# source_eagle.net
KiCad netlist of a schematic drawn in EAGLE
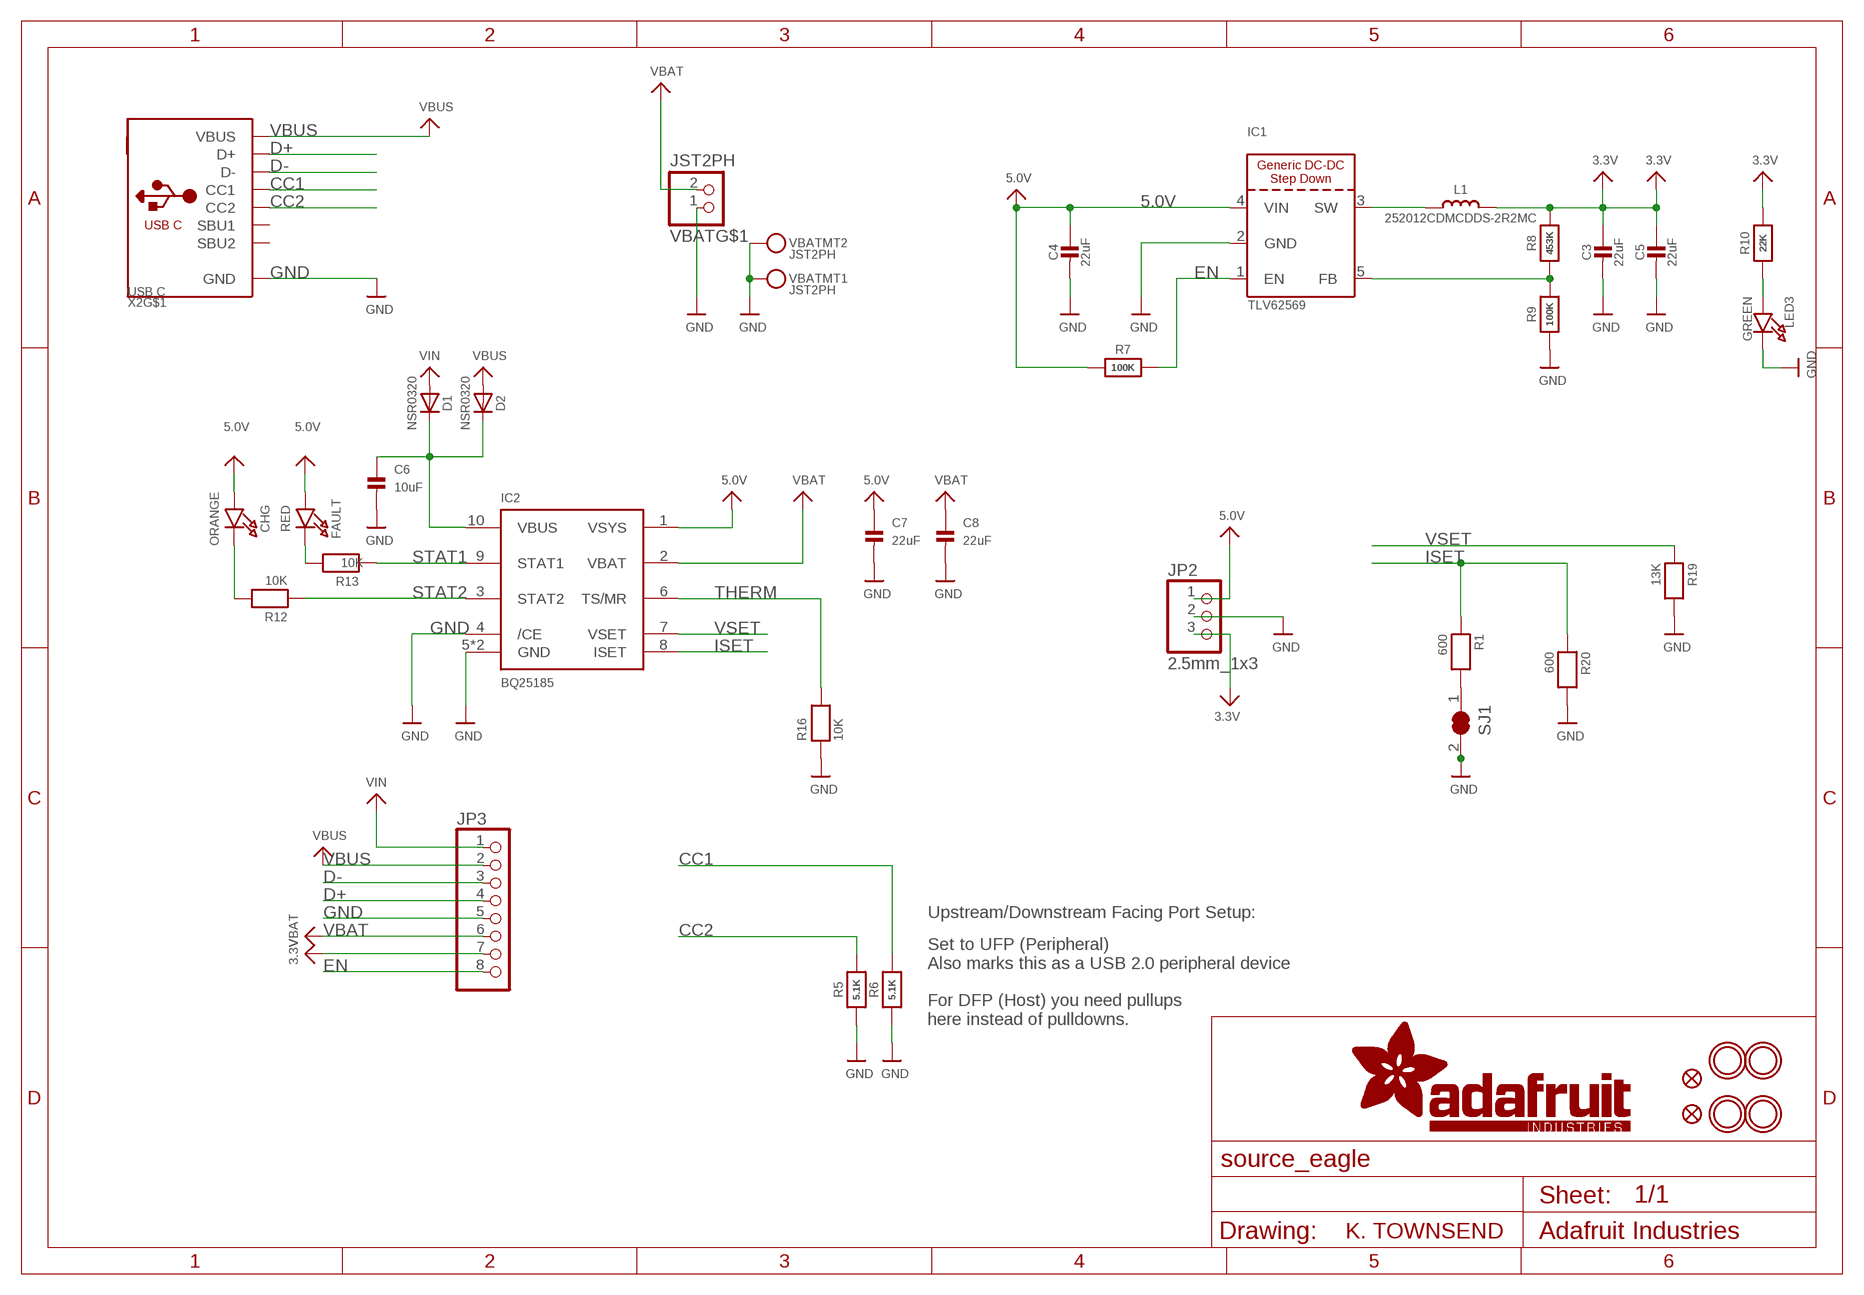
[diagram p0: schematic, sheet 1]

(export (version "E")
  (design (tool "Eeschema 10.0.6"))
  (components
    (comp (ref "C3")
      (value "22uF")
      (footprint "eagle-import:0805-NO")
      (libsource (lib "eagle-import") (part "CAP_CERAMIC0805-NOOUTLINE"))
    )
    (comp (ref "C4")
      (value "22uF")
      (footprint "eagle-import:0805-NO")
      (libsource (lib "eagle-import") (part "CAP_CERAMIC0805-NOOUTLINE"))
    )
    (comp (ref "C5")
      (value "22uF")
      (footprint "eagle-import:0805-NO")
      (libsource (lib "eagle-import") (part "CAP_CERAMIC0805-NOOUTLINE"))
    )
    (comp (ref "C6")
      (value "10uF")
      (footprint "eagle-import:0805-NO")
      (libsource (lib "eagle-import") (part "CAP_CERAMIC0805-NOOUTLINE"))
    )
    (comp (ref "C7")
      (value "22uF")
      (footprint "eagle-import:0805-NO")
      (libsource (lib "eagle-import") (part "CAP_CERAMIC0805-NOOUTLINE"))
    )
    (comp (ref "C8")
      (value "22uF")
      (footprint "eagle-import:0805-NO")
      (libsource (lib "eagle-import") (part "CAP_CERAMIC0805-NOOUTLINE"))
    )
    (comp (ref "CHG")
      (value "ORANGE")
      (footprint "eagle-import:CHIPLED_0603_NOOUTLINE")
      (libsource (lib "eagle-import") (part "LED0603_NOOUTLINE"))
    )
    (comp (ref "D1")
      (value "NSR0320")
      (footprint "eagle-import:SOD-323_MINI")
      (libsource (lib "eagle-import") (part "DIODE_SOD323MINI"))
    )
    (comp (ref "D2")
      (value "NSR0320")
      (footprint "eagle-import:SOD-323_MINI")
      (libsource (lib "eagle-import") (part "DIODE_SOD323MINI"))
    )
    (comp (ref "FAULT")
      (value "RED")
      (footprint "eagle-import:CHIPLED_0603_NOOUTLINE")
      (libsource (lib "eagle-import") (part "LED0603_NOOUTLINE"))
    )
    (comp (ref "FID1")
      (value "FIDUCIAL_0.5MM")
      (footprint "eagle-import:FIDUCIAL_0.5MM")
      (libsource (lib "eagle-import") (part "FIDUCIAL_0.5MM"))
    )
    (comp (ref "FID2")
      (value "FIDUCIAL_0.5MM")
      (footprint "eagle-import:FIDUCIAL_0.5MM")
      (libsource (lib "eagle-import") (part "FIDUCIAL_0.5MM"))
    )
    (comp (ref "IC1")
      (value "TLV62569")
      (footprint "eagle-import:SOT23-5")
      (libsource (lib "eagle-import") (part "VREG_BUCK_5PIN_AP3429/A"))
    )
    (comp (ref "IC2")
      (value "BQ25185")
      (footprint "eagle-import:WSON10")
      (libsource (lib "eagle-import") (part "BQ25185"))
    )
    (comp (ref "JP2")
      (value "2.5mm_1x3")
      (footprint "eagle-import:1X03_2.54MMTERMINAL")
      (libsource (lib "eagle-import") (part "HEADER-1X3_254TERM"))
    )
    (comp (ref "JP3")
      (value "HEADER-1X870MIL")
      (footprint "eagle-import:1X08_ROUND_70")
      (libsource (lib "eagle-import") (part "HEADER-1X870MIL"))
    )
    (comp (ref "L1")
      (value "252012CDMCDDS-2R2MC")
      (footprint "eagle-import:INDUCTOR_TAIYOYUDEN_NRH2412T")
      (libsource (lib "eagle-import") (part "INDUCTORNRH2412T"))
    )
    (comp (ref "LED3")
      (value "GREEN")
      (footprint "eagle-import:CHIPLED_0603_NOOUTLINE")
      (libsource (lib "eagle-import") (part "LED0603_NOOUTLINE"))
    )
    (comp (ref "R1")
      (value "600")
      (footprint "eagle-import:_0402NO")
      (libsource (lib "eagle-import") (part "RESISTOR_0402NO"))
    )
    (comp (ref "R5")
      (value "5.1K")
      (footprint "eagle-import:_0402NO")
      (libsource (lib "eagle-import") (part "RESISTOR_0402NO"))
    )
    (comp (ref "R6")
      (value "5.1K")
      (footprint "eagle-import:_0402NO")
      (libsource (lib "eagle-import") (part "RESISTOR_0402NO"))
    )
    (comp (ref "R7")
      (value "100K")
      (footprint "eagle-import:_0402NO")
      (libsource (lib "eagle-import") (part "RESISTOR_0402NO"))
    )
    (comp (ref "R8")
      (value "453K")
      (footprint "eagle-import:_0402NO")
      (libsource (lib "eagle-import") (part "RESISTOR_0402NO"))
    )
    (comp (ref "R9")
      (value "100K")
      (footprint "eagle-import:_0402NO")
      (libsource (lib "eagle-import") (part "RESISTOR_0402NO"))
    )
    (comp (ref "R10")
      (value "22K")
      (footprint "eagle-import:_0402NO")
      (libsource (lib "eagle-import") (part "RESISTOR_0402NO"))
    )
    (comp (ref "R12")
      (value "10K")
      (footprint "eagle-import:_0402NO")
      (libsource (lib "eagle-import") (part "RESISTOR_0402NO"))
    )
    (comp (ref "R13")
      (value "10K")
      (footprint "eagle-import:_0402NO")
      (libsource (lib "eagle-import") (part "RESISTOR_0402NO"))
    )
    (comp (ref "R16")
      (value "10K")
      (footprint "eagle-import:_0402NO")
      (libsource (lib "eagle-import") (part "RESISTOR_0402NO"))
    )
    (comp (ref "R19")
      (value "13K")
      (footprint "eagle-import:_0402NO")
      (libsource (lib "eagle-import") (part "RESISTOR_0402NO"))
    )
    (comp (ref "R20")
      (value "600")
      (footprint "eagle-import:_0402NO")
      (libsource (lib "eagle-import") (part "RESISTOR_0402NO"))
    )
    (comp (ref "SJ1")
      (value "SOLDERJUMPER_CLOSED")
      (footprint "eagle-import:SOLDERJUMPER_CLOSEDWIRE")
      (libsource (lib "eagle-import") (part "SOLDERJUMPER_CLOSED"))
    )
    (comp (ref "U$9")
      (value "MOUNTINGHOLE2.5")
      (footprint "eagle-import:MOUNTINGHOLE_2.5_PLATED")
      (libsource (lib "eagle-import") (part "MOUNTINGHOLE2.5"))
    )
    (comp (ref "U$10")
      (value "MOUNTINGHOLE2.5")
      (footprint "eagle-import:MOUNTINGHOLE_2.5_PLATED")
      (libsource (lib "eagle-import") (part "MOUNTINGHOLE2.5"))
    )
    (comp (ref "U$11")
      (value "MOUNTINGHOLE2.5")
      (footprint "eagle-import:MOUNTINGHOLE_2.5_PLATED")
      (libsource (lib "eagle-import") (part "MOUNTINGHOLE2.5"))
    )
    (comp (ref "U$12")
      (value "MOUNTINGHOLE2.5")
      (footprint "eagle-import:MOUNTINGHOLE_2.5_PLATED")
      (libsource (lib "eagle-import") (part "MOUNTINGHOLE2.5"))
    )
    (comp (ref "VBAT")
      (value "JST2PH")
      (footprint "eagle-import:JSTPH2_BATT")
      (libsource (lib "eagle-import") (part "CON_JST_PH_2PIN_MT_BATT"))
    )
    (comp (ref "X2")
      (value "USB C")
      (footprint "eagle-import:USB_C_CUSB31-CFM2AX-01-X")
      (libsource (lib "eagle-import") (part "USB_C"))
    )
  )
  (nets
    (net (code "1") (name "/CC1") (class "Default")
      (node (ref "R6") (pin "2") (pinfunction "2_2") (pintype "passive"))
      (node (ref "X2") (pin "A5") (pinfunction "CC1_A5") (pintype "bidirectional"))
    )
    (net (code "2") (name "/CC2") (class "Default")
      (node (ref "R5") (pin "2") (pinfunction "2_2") (pintype "passive"))
      (node (ref "X2") (pin "B5") (pinfunction "CC2_B5") (pintype "bidirectional"))
    )
    (net (code "3") (name "/D+") (class "Default")
      (node (ref "JP3") (pin "4") (pinfunction "4_4") (pintype "passive"))
      (node (ref "X2") (pin "A6") (pinfunction "D+_A6") (pintype "bidirectional"))
      (node (ref "X2") (pin "B6") (pinfunction "D+_B6") (pintype "bidirectional"))
    )
    (net (code "4") (name "/D-") (class "Default")
      (node (ref "JP3") (pin "3") (pinfunction "3_3") (pintype "passive"))
      (node (ref "X2") (pin "A7") (pinfunction "D-_A7") (pintype "bidirectional"))
      (node (ref "X2") (pin "B7") (pinfunction "D-_B7") (pintype "bidirectional"))
    )
    (net (code "5") (name "/EN") (class "Default")
      (node (ref "IC1") (pin "1") (pinfunction "EN_1") (pintype "input"))
      (node (ref "JP3") (pin "8") (pinfunction "8_8") (pintype "passive"))
      (node (ref "R7") (pin "2") (pinfunction "2_2") (pintype "passive"))
    )
    (net (code "6") (name "/ISET") (class "Default")
      (node (ref "IC2") (pin "8") (pinfunction "ISET_8") (pintype "bidirectional"))
      (node (ref "R1") (pin "1") (pinfunction "1_1") (pintype "passive"))
      (node (ref "R20") (pin "1") (pinfunction "1_1") (pintype "passive"))
    )
    (net (code "7") (name "/STAT1") (class "Default")
      (node (ref "IC2") (pin "9") (pinfunction "STAT1_9") (pintype "bidirectional"))
      (node (ref "R13") (pin "1") (pinfunction "1_1") (pintype "passive"))
    )
    (net (code "8") (name "/STAT2") (class "Default")
      (node (ref "IC2") (pin "3") (pinfunction "STAT2_3") (pintype "bidirectional"))
      (node (ref "R12") (pin "1") (pinfunction "1_1") (pintype "passive"))
    )
    (net (code "9") (name "/THERM") (class "Default")
      (node (ref "IC2") (pin "6") (pinfunction "TS/MR_6") (pintype "bidirectional"))
      (node (ref "R16") (pin "2") (pinfunction "2_2") (pintype "passive"))
    )
    (net (code "10") (name "/VSET") (class "Default")
      (node (ref "IC2") (pin "7") (pinfunction "VSET_7") (pintype "bidirectional"))
      (node (ref "R19") (pin "1") (pinfunction "1_1") (pintype "passive"))
    )
    (net (code "11") (name "3.3V") (class "Default")
      (node (ref "C3") (pin "1") (pinfunction "1_1") (pintype "passive"))
      (node (ref "C5") (pin "1") (pinfunction "1_1") (pintype "passive"))
      (node (ref "JP2") (pin "3") (pinfunction "3_3") (pintype "passive"))
      (node (ref "JP3") (pin "7") (pinfunction "7_7") (pintype "passive"))
      (node (ref "L1") (pin "2") (pinfunction "2_2") (pintype "passive"))
      (node (ref "R10") (pin "2") (pinfunction "2_2") (pintype "passive"))
      (node (ref "R8") (pin "2") (pinfunction "2_2") (pintype "passive"))
    )
    (net (code "12") (name "5.0V") (class "Default")
      (node (ref "C4") (pin "1") (pinfunction "1_1") (pintype "passive"))
      (node (ref "C7") (pin "1") (pinfunction "1_1") (pintype "passive"))
      (node (ref "CHG") (pin "A") (pinfunction "A_A") (pintype "passive"))
      (node (ref "FAULT") (pin "A") (pinfunction "A_A") (pintype "passive"))
      (node (ref "IC1") (pin "4") (pinfunction "VIN_4") (pintype "power_in"))
      (node (ref "IC2") (pin "1") (pinfunction "VSYS_1") (pintype "power_in"))
      (node (ref "JP2") (pin "1") (pinfunction "1_1") (pintype "passive"))
      (node (ref "R7") (pin "1") (pinfunction "1_1") (pintype "passive"))
    )
    (net (code "13") (name "GND") (class "Default")
      (node (ref "C3") (pin "2") (pinfunction "2_2") (pintype "passive"))
      (node (ref "C4") (pin "2") (pinfunction "2_2") (pintype "passive"))
      (node (ref "C5") (pin "2") (pinfunction "2_2") (pintype "passive"))
      (node (ref "C6") (pin "2") (pinfunction "2_2") (pintype "passive"))
      (node (ref "C7") (pin "2") (pinfunction "2_2") (pintype "passive"))
      (node (ref "C8") (pin "2") (pinfunction "2_2") (pintype "passive"))
      (node (ref "IC1") (pin "2") (pinfunction "GND_2") (pintype "power_in"))
      (node (ref "IC2") (pin "4") (pinfunction "/CE_4") (pintype "input"))
      (node (ref "IC2") (pin "5") (pinfunction "GND_5") (pintype "bidirectional"))
      (node (ref "IC2") (pin "PAD") (pinfunction "GND_PAD") (pintype "bidirectional"))
      (node (ref "JP2") (pin "2") (pinfunction "2_2") (pintype "passive"))
      (node (ref "JP3") (pin "5") (pinfunction "5_5") (pintype "passive"))
      (node (ref "LED3") (pin "C") (pinfunction "C_C") (pintype "passive"))
      (node (ref "R16") (pin "1") (pinfunction "1_1") (pintype "passive"))
      (node (ref "R19") (pin "2") (pinfunction "2_2") (pintype "passive"))
      (node (ref "R20") (pin "2") (pinfunction "2_2") (pintype "passive"))
      (node (ref "R5") (pin "1") (pinfunction "1_1") (pintype "passive"))
      (node (ref "R6") (pin "1") (pinfunction "1_1") (pintype "passive"))
      (node (ref "R9") (pin "1") (pinfunction "1_1") (pintype "passive"))
      (node (ref "SJ1") (pin "2") (pinfunction "2_2") (pintype "passive"))
      (node (ref "VBAT") (pin "1") (pinfunction "1_1") (pintype "passive"))
      (node (ref "VBAT") (pin "NC1") (pinfunction "P$1_NC1") (pintype "bidirectional"))
      (node (ref "VBAT") (pin "NC2") (pinfunction "P$1_NC2") (pintype "bidirectional"))
      (node (ref "X2") (pin "A1B12") (pinfunction "GND_A1B12") (pintype "power_in"))
      (node (ref "X2") (pin "B1A12") (pinfunction "GND_B1A12") (pintype "power_in"))
    )
    (net (code "14") (name "Net-(CHG-PadC)") (class "Default")
      (node (ref "CHG") (pin "C") (pinfunction "C_C") (pintype "passive"))
      (node (ref "R12") (pin "2") (pinfunction "2_2") (pintype "passive"))
    )
    (net (code "15") (name "Net-(FAULT-PadC)") (class "Default")
      (node (ref "FAULT") (pin "C") (pinfunction "C_C") (pintype "passive"))
      (node (ref "R13") (pin "2") (pinfunction "2_2") (pintype "passive"))
    )
    (net (code "16") (name "Net-(IC1-FB)") (class "Default")
      (node (ref "IC1") (pin "5") (pinfunction "FB_5") (pintype "power_in"))
      (node (ref "R8") (pin "1") (pinfunction "1_1") (pintype "passive"))
      (node (ref "R9") (pin "2") (pinfunction "2_2") (pintype "passive"))
    )
    (net (code "17") (name "Net-(IC1-SW)") (class "Default")
      (node (ref "IC1") (pin "3") (pinfunction "SW_3") (pintype "output"))
      (node (ref "L1") (pin "1") (pinfunction "1_1") (pintype "passive"))
    )
    (net (code "18") (name "Net-(IC2-VBUS)") (class "Default")
      (node (ref "C6") (pin "1") (pinfunction "1_1") (pintype "passive"))
      (node (ref "D1") (pin "C") (pinfunction "C_C") (pintype "passive"))
      (node (ref "D2") (pin "C") (pinfunction "C_C") (pintype "passive"))
      (node (ref "IC2") (pin "10") (pinfunction "VBUS_10") (pintype "power_in"))
    )
    (net (code "19") (name "Net-(LED3-PadA)") (class "Default")
      (node (ref "LED3") (pin "A") (pinfunction "A_A") (pintype "passive"))
      (node (ref "R10") (pin "1") (pinfunction "1_1") (pintype "passive"))
    )
    (net (code "20") (name "Net-(R1-Pad2)") (class "Default")
      (node (ref "R1") (pin "2") (pinfunction "2_2") (pintype "passive"))
      (node (ref "SJ1") (pin "1") (pinfunction "1_1") (pintype "passive"))
    )
    (net (code "21") (name "VBAT") (class "Default")
      (node (ref "C8") (pin "1") (pinfunction "1_1") (pintype "passive"))
      (node (ref "IC2") (pin "2") (pinfunction "VBAT_2") (pintype "input"))
      (node (ref "JP3") (pin "6") (pinfunction "6_6") (pintype "passive"))
      (node (ref "VBAT") (pin "2") (pinfunction "2_2") (pintype "passive"))
    )
    (net (code "22") (name "VBUS") (class "Default")
      (node (ref "D2") (pin "A") (pinfunction "A_A") (pintype "passive"))
      (node (ref "JP3") (pin "2") (pinfunction "2_2") (pintype "passive"))
      (node (ref "X2") (pin "A4B9") (pinfunction "VBUS_A4B9") (pintype "power_in"))
      (node (ref "X2") (pin "B4A9") (pinfunction "VBUS_B4A9") (pintype "power_in"))
    )
    (net (code "23") (name "VIN") (class "Default")
      (node (ref "D1") (pin "A") (pinfunction "A_A") (pintype "passive"))
      (node (ref "JP3") (pin "1") (pinfunction "1_1") (pintype "passive"))
    )
    (net (code "24") (name "unconnected-(X2A-SBU1-PadA8)") (class "Default")
      (node (ref "X2") (pin "A8") (pinfunction "SBU1_A8") (pintype "bidirectional"))
    )
    (net (code "25") (name "unconnected-(X2A-SBU2-PadB8)") (class "Default")
      (node (ref "X2") (pin "B8") (pinfunction "SBU2_B8") (pintype "bidirectional"))
    )
  )
)
